# Smarttree_CMU_4.net
KiCad netlist of a schematic drawn in EAGLE
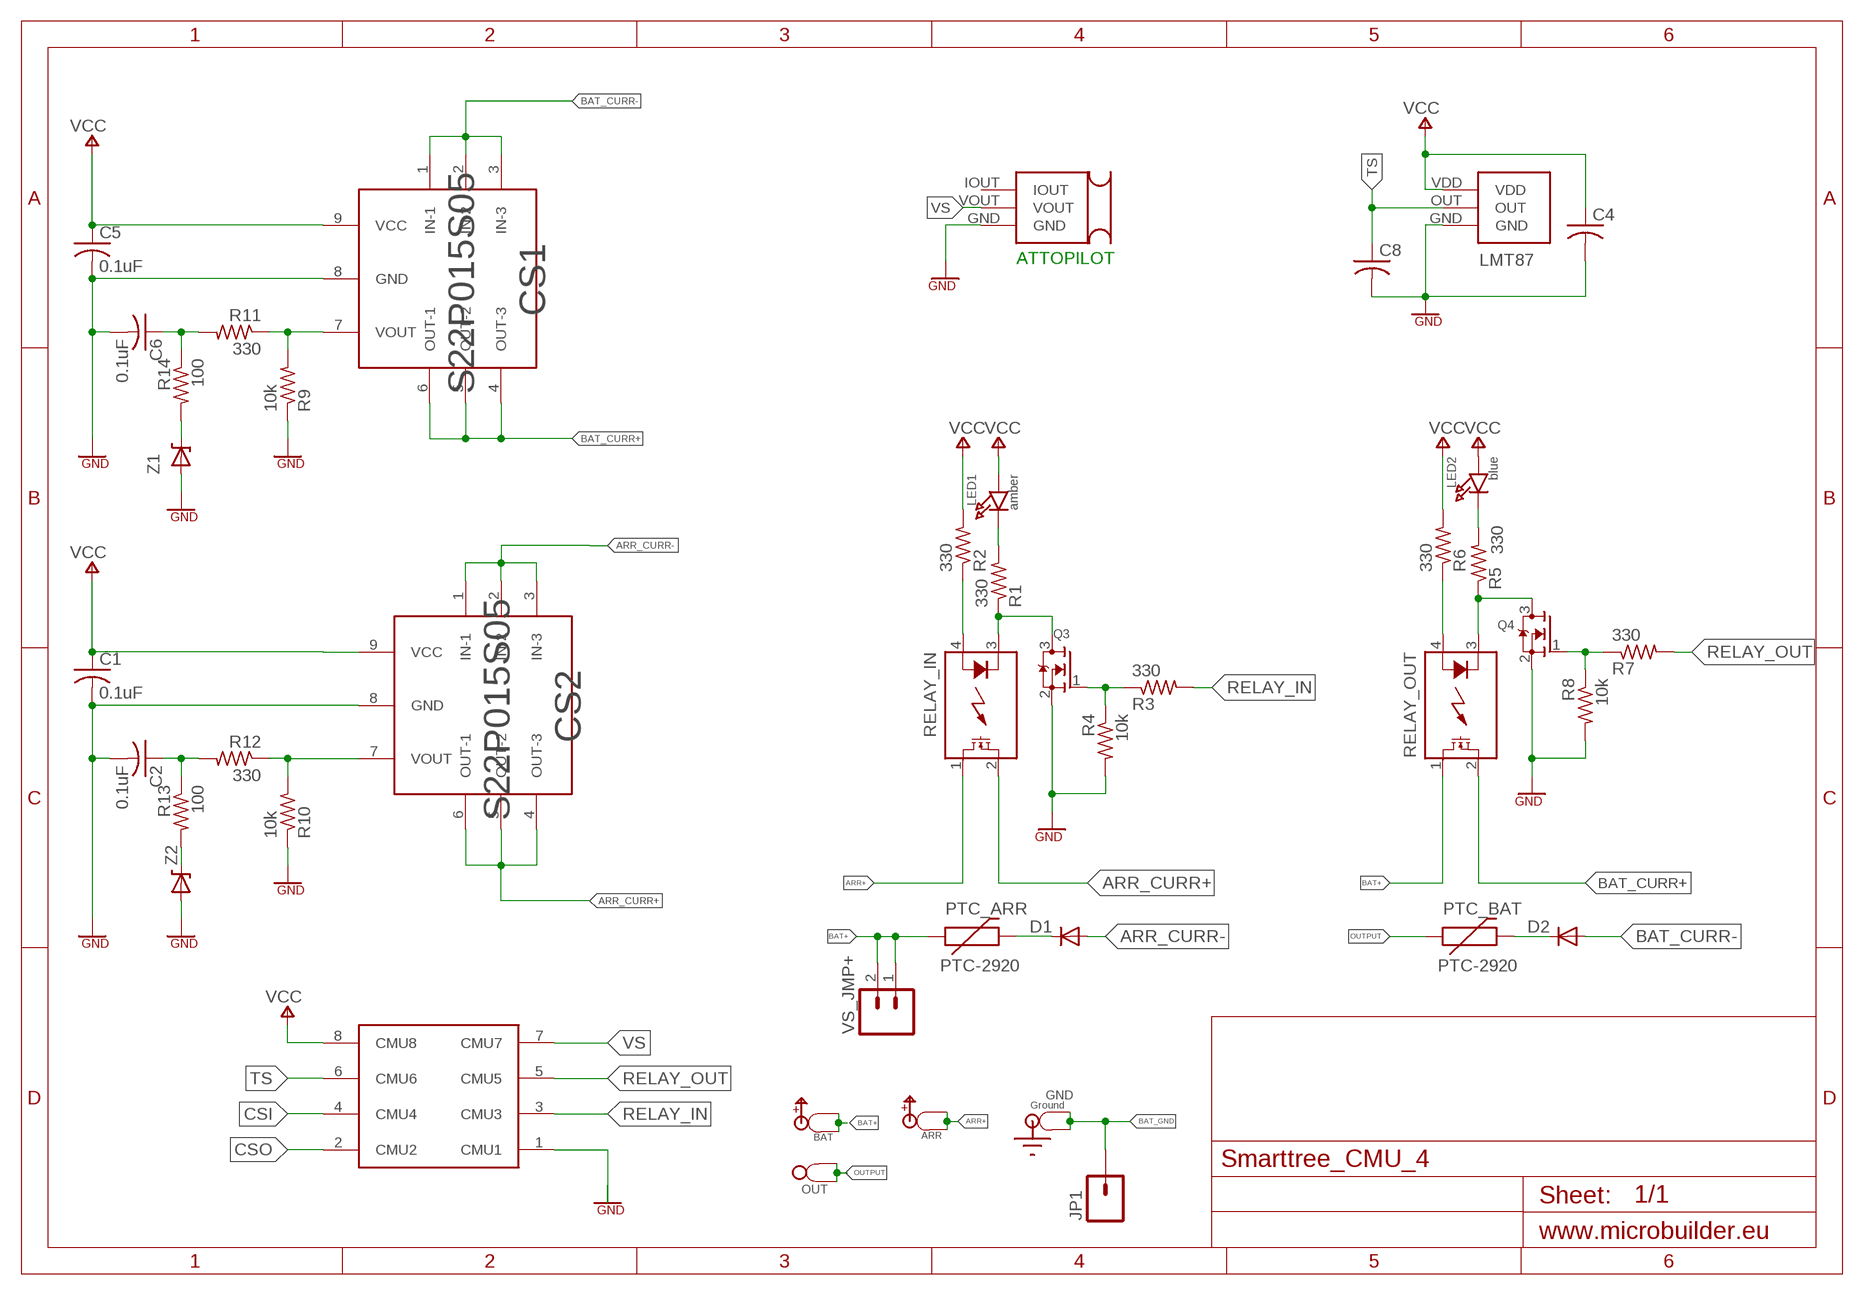
[diagram p0: schematic, sheet 1]

(export (version "E")
  (design (tool "Eeschema 10.0.6"))
  (components
    (comp (ref "ARR")
      (value "SPADE-POWER")
      (footprint "eagle-import:SPADE-POWER")
      (libsource (lib "eagle-import") (part "SPADE-POWER"))
    )
    (comp (ref "ATTOPILOT")
      (value "ATTOPILOT_VOLT")
      (footprint "eagle-import:TH_BKOT")
      (libsource (lib "eagle-import") (part "ATTOPILOT_VOLT"))
    )
    (comp (ref "BAT")
      (value "SPADE-POWER")
      (footprint "eagle-import:SPADE-POWER")
      (libsource (lib "eagle-import") (part "SPADE-POWER"))
    )
    (comp (ref "C1")
      (value "0.1uF")
      (footprint "eagle-import:C0805")
      (libsource (lib "eagle-import") (part "C-USC0805"))
    )
    (comp (ref "C2")
      (value "0.1uF")
      (footprint "eagle-import:C0805")
      (libsource (lib "eagle-import") (part "C-USC0805"))
    )
    (comp (ref "C4")
      (value "C-USC0805")
      (footprint "eagle-import:C0805")
      (libsource (lib "eagle-import") (part "C-USC0805"))
    )
    (comp (ref "C5")
      (value "0.1uF")
      (footprint "eagle-import:C0805")
      (libsource (lib "eagle-import") (part "C-USC0805"))
    )
    (comp (ref "C6")
      (value "0.1uF")
      (footprint "eagle-import:C0805")
      (libsource (lib "eagle-import") (part "C-USC0805"))
    )
    (comp (ref "C8")
      (value "C-USC0805")
      (footprint "eagle-import:C0805")
      (libsource (lib "eagle-import") (part "C-USC0805"))
    )
    (comp (ref "CS1")
      (value "S22P015S05")
      (footprint "eagle-import:S22P015S05")
      (libsource (lib "eagle-import") (part "S22P015S05"))
    )
    (comp (ref "CS2")
      (value "S22P015S05")
      (footprint "eagle-import:S22P015S05")
      (libsource (lib "eagle-import") (part "S22P015S05"))
    )
    (comp (ref "D1")
      (value "DIODE-SOD106-R")
      (footprint "eagle-import:SOD106-R")
      (libsource (lib "eagle-import") (part "DIODE-SOD106-R"))
    )
    (comp (ref "D2")
      (value "DIODE-SOD106-R")
      (footprint "eagle-import:SOD106-R")
      (libsource (lib "eagle-import") (part "DIODE-SOD106-R"))
    )
    (comp (ref "GND")
      (value "SPADE-GROUND")
      (footprint "eagle-import:SPADE-GROUND")
      (libsource (lib "eagle-import") (part "SPADE-GROUND"))
    )
    (comp (ref "JP1")
      (value "M01OFFSET")
      (footprint "eagle-import:1X01_OFFSET")
      (libsource (lib "eagle-import") (part "M01OFFSET"))
    )
    (comp (ref "LED1")
      (value "amber")
      (footprint "eagle-import:CHIPLED_0805")
      (libsource (lib "eagle-import") (part "LED0805"))
    )
    (comp (ref "LED2")
      (value "blue")
      (footprint "eagle-import:CHIPLED_0805")
      (libsource (lib "eagle-import") (part "LED0805"))
    )
    (comp (ref "LMT87")
      (value "LMT87_PAC")
      (footprint "eagle-import:LMT87_TO")
      (libsource (lib "eagle-import") (part "LMT87_PAC"))
    )
    (comp (ref "OUT")
      (value "SPADE-TERMINALPTH")
      (footprint "eagle-import:SPADE-TERMINAL")
      (libsource (lib "eagle-import") (part "SPADE-TERMINALPTH"))
    )
    (comp (ref "PTC_ARR")
      (value "PTC-2920")
      (footprint "eagle-import:PTC-2920")
      (libsource (lib "eagle-import") (part "PTC-2920"))
    )
    (comp (ref "PTC_BAT")
      (value "PTC-2920")
      (footprint "eagle-import:PTC-2920")
      (libsource (lib "eagle-import") (part "PTC-2920"))
    )
    (comp (ref "Q3")
      (value "MOSFET-NREFLOW")
      (footprint "eagle-import:SOT23")
      (libsource (lib "eagle-import") (part "MOSFET-NREFLOW"))
    )
    (comp (ref "Q4")
      (value "MOSFET-NREFLOW")
      (footprint "eagle-import:SOT23")
      (libsource (lib "eagle-import") (part "MOSFET-NREFLOW"))
    )
    (comp (ref "R1")
      (value "330")
      (footprint "eagle-import:R0805")
      (libsource (lib "eagle-import") (part "R-US_R0805"))
    )
    (comp (ref "R2")
      (value "330")
      (footprint "eagle-import:R0805")
      (libsource (lib "eagle-import") (part "R-US_R0805"))
    )
    (comp (ref "R3")
      (value "330")
      (footprint "eagle-import:R0805")
      (libsource (lib "eagle-import") (part "R-US_R0805"))
    )
    (comp (ref "R4")
      (value "10k")
      (footprint "eagle-import:R0805")
      (libsource (lib "eagle-import") (part "R-US_R0805"))
    )
    (comp (ref "R5")
      (value "330")
      (footprint "eagle-import:R0805")
      (libsource (lib "eagle-import") (part "R-US_R0805"))
    )
    (comp (ref "R6")
      (value "330")
      (footprint "eagle-import:R0805")
      (libsource (lib "eagle-import") (part "R-US_R0805"))
    )
    (comp (ref "R7")
      (value "330")
      (footprint "eagle-import:R0805")
      (libsource (lib "eagle-import") (part "R-US_R0805"))
    )
    (comp (ref "R8")
      (value "10k")
      (footprint "eagle-import:R0805")
      (libsource (lib "eagle-import") (part "R-US_R0805"))
    )
    (comp (ref "R9")
      (value "10k")
      (footprint "eagle-import:R0805")
      (libsource (lib "eagle-import") (part "R-US_R0805"))
    )
    (comp (ref "R10")
      (value "10k")
      (footprint "eagle-import:R0805")
      (libsource (lib "eagle-import") (part "R-US_R0805"))
    )
    (comp (ref "R11")
      (value "330")
      (footprint "eagle-import:R0805")
      (libsource (lib "eagle-import") (part "R-US_R0805"))
    )
    (comp (ref "R12")
      (value "330")
      (footprint "eagle-import:R0805")
      (libsource (lib "eagle-import") (part "R-US_R0805"))
    )
    (comp (ref "R13")
      (value "100")
      (footprint "eagle-import:R0805")
      (libsource (lib "eagle-import") (part "R-US_R0805"))
    )
    (comp (ref "R14")
      (value "100")
      (footprint "eagle-import:R0805")
      (libsource (lib "eagle-import") (part "R-US_R0805"))
    )
    (comp (ref "RELAY_IN")
      (value "CPC1708J")
      (footprint "eagle-import:I4-PAC")
      (libsource (lib "eagle-import") (part "CPC1708J"))
    )
    (comp (ref "RELAY_OUT")
      (value "CPC1708J")
      (footprint "eagle-import:I4-PAC")
      (libsource (lib "eagle-import") (part "CPC1708J"))
    )
    (comp (ref "U$1")
      (value "8PINCONN")
      (footprint "eagle-import:8PINCONN")
      (libsource (lib "eagle-import") (part "8PINCONN"))
    )
    (comp (ref "VS_JMP+")
      (value "M02")
      (footprint "eagle-import:1X02_LONGPADS")
      (libsource (lib "eagle-import") (part "M02"))
    )
    (comp (ref "Z1")
      (value "DIODE-ZENER-BZT52")
      (footprint "eagle-import:SOD-323")
      (libsource (lib "eagle-import") (part "DIODE-ZENER-BZT52"))
    )
    (comp (ref "Z2")
      (value "DIODE-ZENER-BZT52")
      (footprint "eagle-import:SOD-323")
      (libsource (lib "eagle-import") (part "DIODE-ZENER-BZT52"))
    )
  )
  (nets
    (net (code "1") (name "5V") (class "Default")
      (node (ref "C1") (pin "1") (pinfunction "1_1") (pintype "passive"))
      (node (ref "C4") (pin "1") (pinfunction "1_1") (pintype "passive"))
      (node (ref "C5") (pin "1") (pinfunction "1_1") (pintype "passive"))
      (node (ref "CS1") (pin "9") (pinfunction "VCC_9") (pintype "bidirectional"))
      (node (ref "CS2") (pin "9") (pinfunction "VCC_9") (pintype "bidirectional"))
      (node (ref "LED1") (pin "A") (pinfunction "A_A") (pintype "passive"))
      (node (ref "LED2") (pin "A") (pinfunction "A_A") (pintype "passive"))
      (node (ref "LMT87") (pin "VDD") (pinfunction "VDD_VDD") (pintype "bidirectional"))
      (node (ref "R2") (pin "2") (pinfunction "2_2") (pintype "passive"))
      (node (ref "R6") (pin "2") (pinfunction "2_2") (pintype "passive"))
      (node (ref "U$1") (pin "8") (pinfunction "CMU8_8") (pintype "bidirectional"))
    )
    (net (code "2") (name "ARR+") (class "Default")
      (node (ref "ARR") (pin "P$1") (pinfunction "P$1_P$1") (pintype "bidirectional"))
      (node (ref "ARR") (pin "P$2") (pinfunction "P$2_P$2") (pintype "bidirectional"))
      (node (ref "RELAY_IN") (pin "1") (pinfunction "DS1_1") (pintype "passive"))
    )
    (net (code "3") (name "ARR_CURR+") (class "Default")
      (node (ref "CS2") (pin "4") (pinfunction "OUT-3_4") (pintype "bidirectional"))
      (node (ref "CS2") (pin "5") (pinfunction "OUT-2_5") (pintype "bidirectional"))
      (node (ref "CS2") (pin "6") (pinfunction "OUT-1_6") (pintype "bidirectional"))
      (node (ref "RELAY_IN") (pin "2") (pinfunction "DS2_2") (pintype "passive"))
    )
    (net (code "4") (name "ARR_CURR-") (class "Default")
      (node (ref "CS2") (pin "1") (pinfunction "IN-1_1") (pintype "bidirectional"))
      (node (ref "CS2") (pin "2") (pinfunction "IN-2_2") (pintype "bidirectional"))
      (node (ref "CS2") (pin "3") (pinfunction "IN-3_3") (pintype "bidirectional"))
      (node (ref "D1") (pin "A") (pinfunction "A_A") (pintype "passive"))
    )
    (net (code "5") (name "BAT+") (class "Default")
      (node (ref "BAT") (pin "P$1") (pinfunction "P$1_P$1") (pintype "bidirectional"))
      (node (ref "BAT") (pin "P$2") (pinfunction "P$2_P$2") (pintype "bidirectional"))
      (node (ref "PTC_ARR") (pin "1") (pinfunction "1_1") (pintype "bidirectional"))
      (node (ref "RELAY_OUT") (pin "1") (pinfunction "DS1_1") (pintype "passive"))
      (node (ref "VS_JMP+") (pin "1") (pinfunction "1_1") (pintype "passive"))
      (node (ref "VS_JMP+") (pin "2") (pinfunction "2_2") (pintype "passive"))
    )
    (net (code "6") (name "BAT_CURR+") (class "Default")
      (node (ref "CS1") (pin "4") (pinfunction "OUT-3_4") (pintype "bidirectional"))
      (node (ref "CS1") (pin "5") (pinfunction "OUT-2_5") (pintype "bidirectional"))
      (node (ref "CS1") (pin "6") (pinfunction "OUT-1_6") (pintype "bidirectional"))
      (node (ref "RELAY_OUT") (pin "2") (pinfunction "DS2_2") (pintype "passive"))
    )
    (net (code "7") (name "BAT_CURR-") (class "Default")
      (node (ref "CS1") (pin "1") (pinfunction "IN-1_1") (pintype "bidirectional"))
      (node (ref "CS1") (pin "2") (pinfunction "IN-2_2") (pintype "bidirectional"))
      (node (ref "CS1") (pin "3") (pinfunction "IN-3_3") (pintype "bidirectional"))
      (node (ref "D2") (pin "A") (pinfunction "A_A") (pintype "passive"))
    )
    (net (code "8") (name "BAT_GND") (class "Default")
      (node (ref "GND") (pin "P$1") (pinfunction "P$1_P$1") (pintype "bidirectional"))
      (node (ref "GND") (pin "P$2") (pinfunction "P$2_P$2") (pintype "bidirectional"))
      (node (ref "JP1") (pin "1") (pinfunction "1_1") (pintype "passive"))
    )
    (net (code "9") (name "CSI") (class "Default")
      (node (ref "C2") (pin "1") (pinfunction "1_1") (pintype "passive"))
      (node (ref "R12") (pin "2") (pinfunction "2_2") (pintype "passive"))
      (node (ref "R13") (pin "1") (pinfunction "1_1") (pintype "passive"))
      (node (ref "U$1") (pin "4") (pinfunction "CMU4_4") (pintype "bidirectional"))
    )
    (net (code "10") (name "CSO") (class "Default")
      (node (ref "C6") (pin "1") (pinfunction "1_1") (pintype "passive"))
      (node (ref "R11") (pin "2") (pinfunction "2_2") (pintype "passive"))
      (node (ref "R14") (pin "1") (pinfunction "1_1") (pintype "passive"))
      (node (ref "U$1") (pin "2") (pinfunction "CMU2_2") (pintype "bidirectional"))
    )
    (net (code "11") (name "GND") (class "Default")
      (node (ref "ATTOPILOT") (pin "GND") (pinfunction "GND_GND") (pintype "bidirectional"))
      (node (ref "C1") (pin "2") (pinfunction "2_2") (pintype "passive"))
      (node (ref "C2") (pin "2") (pinfunction "2_2") (pintype "passive"))
      (node (ref "C4") (pin "2") (pinfunction "2_2") (pintype "passive"))
      (node (ref "C5") (pin "2") (pinfunction "2_2") (pintype "passive"))
      (node (ref "C6") (pin "2") (pinfunction "2_2") (pintype "passive"))
      (node (ref "C8") (pin "2") (pinfunction "2_2") (pintype "passive"))
      (node (ref "CS1") (pin "8") (pinfunction "GND_8") (pintype "bidirectional"))
      (node (ref "CS2") (pin "8") (pinfunction "GND_8") (pintype "bidirectional"))
      (node (ref "LMT87") (pin "GND") (pinfunction "GND_GND") (pintype "bidirectional"))
      (node (ref "Q3") (pin "2") (pinfunction "S_2") (pintype "bidirectional"))
      (node (ref "Q4") (pin "2") (pinfunction "S_2") (pintype "bidirectional"))
      (node (ref "R10") (pin "1") (pinfunction "1_1") (pintype "passive"))
      (node (ref "R4") (pin "2") (pinfunction "2_2") (pintype "passive"))
      (node (ref "R8") (pin "2") (pinfunction "2_2") (pintype "passive"))
      (node (ref "R9") (pin "1") (pinfunction "1_1") (pintype "passive"))
      (node (ref "U$1") (pin "1") (pinfunction "CMU1_1") (pintype "bidirectional"))
      (node (ref "Z1") (pin "2") (pinfunction "A_2") (pintype "passive"))
      (node (ref "Z2") (pin "2") (pinfunction "A_2") (pintype "passive"))
    )
    (net (code "12") (name "Net-(CS1-VOUT)") (class "Default")
      (node (ref "CS1") (pin "7") (pinfunction "VOUT_7") (pintype "bidirectional"))
      (node (ref "R11") (pin "1") (pinfunction "1_1") (pintype "passive"))
      (node (ref "R9") (pin "2") (pinfunction "2_2") (pintype "passive"))
    )
    (net (code "13") (name "Net-(CS2-VOUT)") (class "Default")
      (node (ref "CS2") (pin "7") (pinfunction "VOUT_7") (pintype "bidirectional"))
      (node (ref "R10") (pin "2") (pinfunction "2_2") (pintype "passive"))
      (node (ref "R12") (pin "1") (pinfunction "1_1") (pintype "passive"))
    )
    (net (code "14") (name "Net-(D1-PadC)") (class "Default")
      (node (ref "D1") (pin "C") (pinfunction "C_C") (pintype "passive"))
      (node (ref "PTC_ARR") (pin "2") (pinfunction "2_2") (pintype "bidirectional"))
    )
    (net (code "15") (name "Net-(D2-PadC)") (class "Default")
      (node (ref "D2") (pin "C") (pinfunction "C_C") (pintype "passive"))
      (node (ref "PTC_BAT") (pin "2") (pinfunction "2_2") (pintype "bidirectional"))
    )
    (net (code "16") (name "Net-(LED1-PadC)") (class "Default")
      (node (ref "LED1") (pin "C") (pinfunction "C_C") (pintype "passive"))
      (node (ref "R1") (pin "2") (pinfunction "2_2") (pintype "passive"))
    )
    (net (code "17") (name "Net-(LED2-PadC)") (class "Default")
      (node (ref "LED2") (pin "C") (pinfunction "C_C") (pintype "passive"))
      (node (ref "R5") (pin "2") (pinfunction "2_2") (pintype "passive"))
    )
    (net (code "18") (name "Net-(Q3-D)") (class "Default")
      (node (ref "Q3") (pin "3") (pinfunction "D_3") (pintype "bidirectional"))
      (node (ref "R1") (pin "1") (pinfunction "1_1") (pintype "passive"))
      (node (ref "RELAY_IN") (pin "3") (pinfunction "K_3") (pintype "passive"))
    )
    (net (code "19") (name "Net-(Q3-G)") (class "Default")
      (node (ref "Q3") (pin "1") (pinfunction "G_1") (pintype "bidirectional"))
      (node (ref "R3") (pin "1") (pinfunction "1_1") (pintype "passive"))
      (node (ref "R4") (pin "1") (pinfunction "1_1") (pintype "passive"))
    )
    (net (code "20") (name "Net-(Q4-D)") (class "Default")
      (node (ref "Q4") (pin "3") (pinfunction "D_3") (pintype "bidirectional"))
      (node (ref "R5") (pin "1") (pinfunction "1_1") (pintype "passive"))
      (node (ref "RELAY_OUT") (pin "3") (pinfunction "K_3") (pintype "passive"))
    )
    (net (code "21") (name "Net-(Q4-G)") (class "Default")
      (node (ref "Q4") (pin "1") (pinfunction "G_1") (pintype "bidirectional"))
      (node (ref "R7") (pin "1") (pinfunction "1_1") (pintype "passive"))
      (node (ref "R8") (pin "1") (pinfunction "1_1") (pintype "passive"))
    )
    (net (code "22") (name "Net-(RELAY_IN-A)") (class "Default")
      (node (ref "R2") (pin "1") (pinfunction "1_1") (pintype "passive"))
      (node (ref "RELAY_IN") (pin "4") (pinfunction "A_4") (pintype "passive"))
    )
    (net (code "23") (name "Net-(RELAY_OUT-A)") (class "Default")
      (node (ref "R6") (pin "1") (pinfunction "1_1") (pintype "passive"))
      (node (ref "RELAY_OUT") (pin "4") (pinfunction "A_4") (pintype "passive"))
    )
    (net (code "24") (name "Net-(Z1-C)") (class "Default")
      (node (ref "R14") (pin "2") (pinfunction "2_2") (pintype "passive"))
      (node (ref "Z1") (pin "1") (pinfunction "C_1") (pintype "passive"))
    )
    (net (code "25") (name "Net-(Z2-C)") (class "Default")
      (node (ref "R13") (pin "2") (pinfunction "2_2") (pintype "passive"))
      (node (ref "Z2") (pin "1") (pinfunction "C_1") (pintype "passive"))
    )
    (net (code "26") (name "OUTPUT") (class "Default")
      (node (ref "OUT") (pin "P$1") (pinfunction "P$1_P$1") (pintype "bidirectional"))
      (node (ref "OUT") (pin "P$2") (pinfunction "P$2_P$2") (pintype "bidirectional"))
      (node (ref "PTC_BAT") (pin "1") (pinfunction "1_1") (pintype "bidirectional"))
    )
    (net (code "27") (name "RELAY_IN") (class "Default")
      (node (ref "R3") (pin "2") (pinfunction "2_2") (pintype "passive"))
      (node (ref "U$1") (pin "3") (pinfunction "CMU3_3") (pintype "bidirectional"))
    )
    (net (code "28") (name "RELAY_OUT") (class "Default")
      (node (ref "R7") (pin "2") (pinfunction "2_2") (pintype "passive"))
      (node (ref "U$1") (pin "5") (pinfunction "CMU5_5") (pintype "bidirectional"))
    )
    (net (code "29") (name "TS") (class "Default")
      (node (ref "C8") (pin "1") (pinfunction "1_1") (pintype "passive"))
      (node (ref "LMT87") (pin "OUT") (pinfunction "OUT_OUT") (pintype "bidirectional"))
      (node (ref "U$1") (pin "6") (pinfunction "CMU6_6") (pintype "bidirectional"))
    )
    (net (code "30") (name "VS") (class "Default")
      (node (ref "ATTOPILOT") (pin "VOUT") (pinfunction "VOUT_VOUT") (pintype "bidirectional"))
      (node (ref "U$1") (pin "7") (pinfunction "CMU7_7") (pintype "bidirectional"))
    )
    (net (code "31") (name "unconnected-(ATTOPILOT-PadIOUT)") (class "Default")
      (node (ref "ATTOPILOT") (pin "IOUT") (pinfunction "IOUT_IOUT") (pintype "bidirectional"))
    )
  )
)
